# pc_rpimax30205_brk.net
KiCad netlist of a schematic drawn in EAGLE
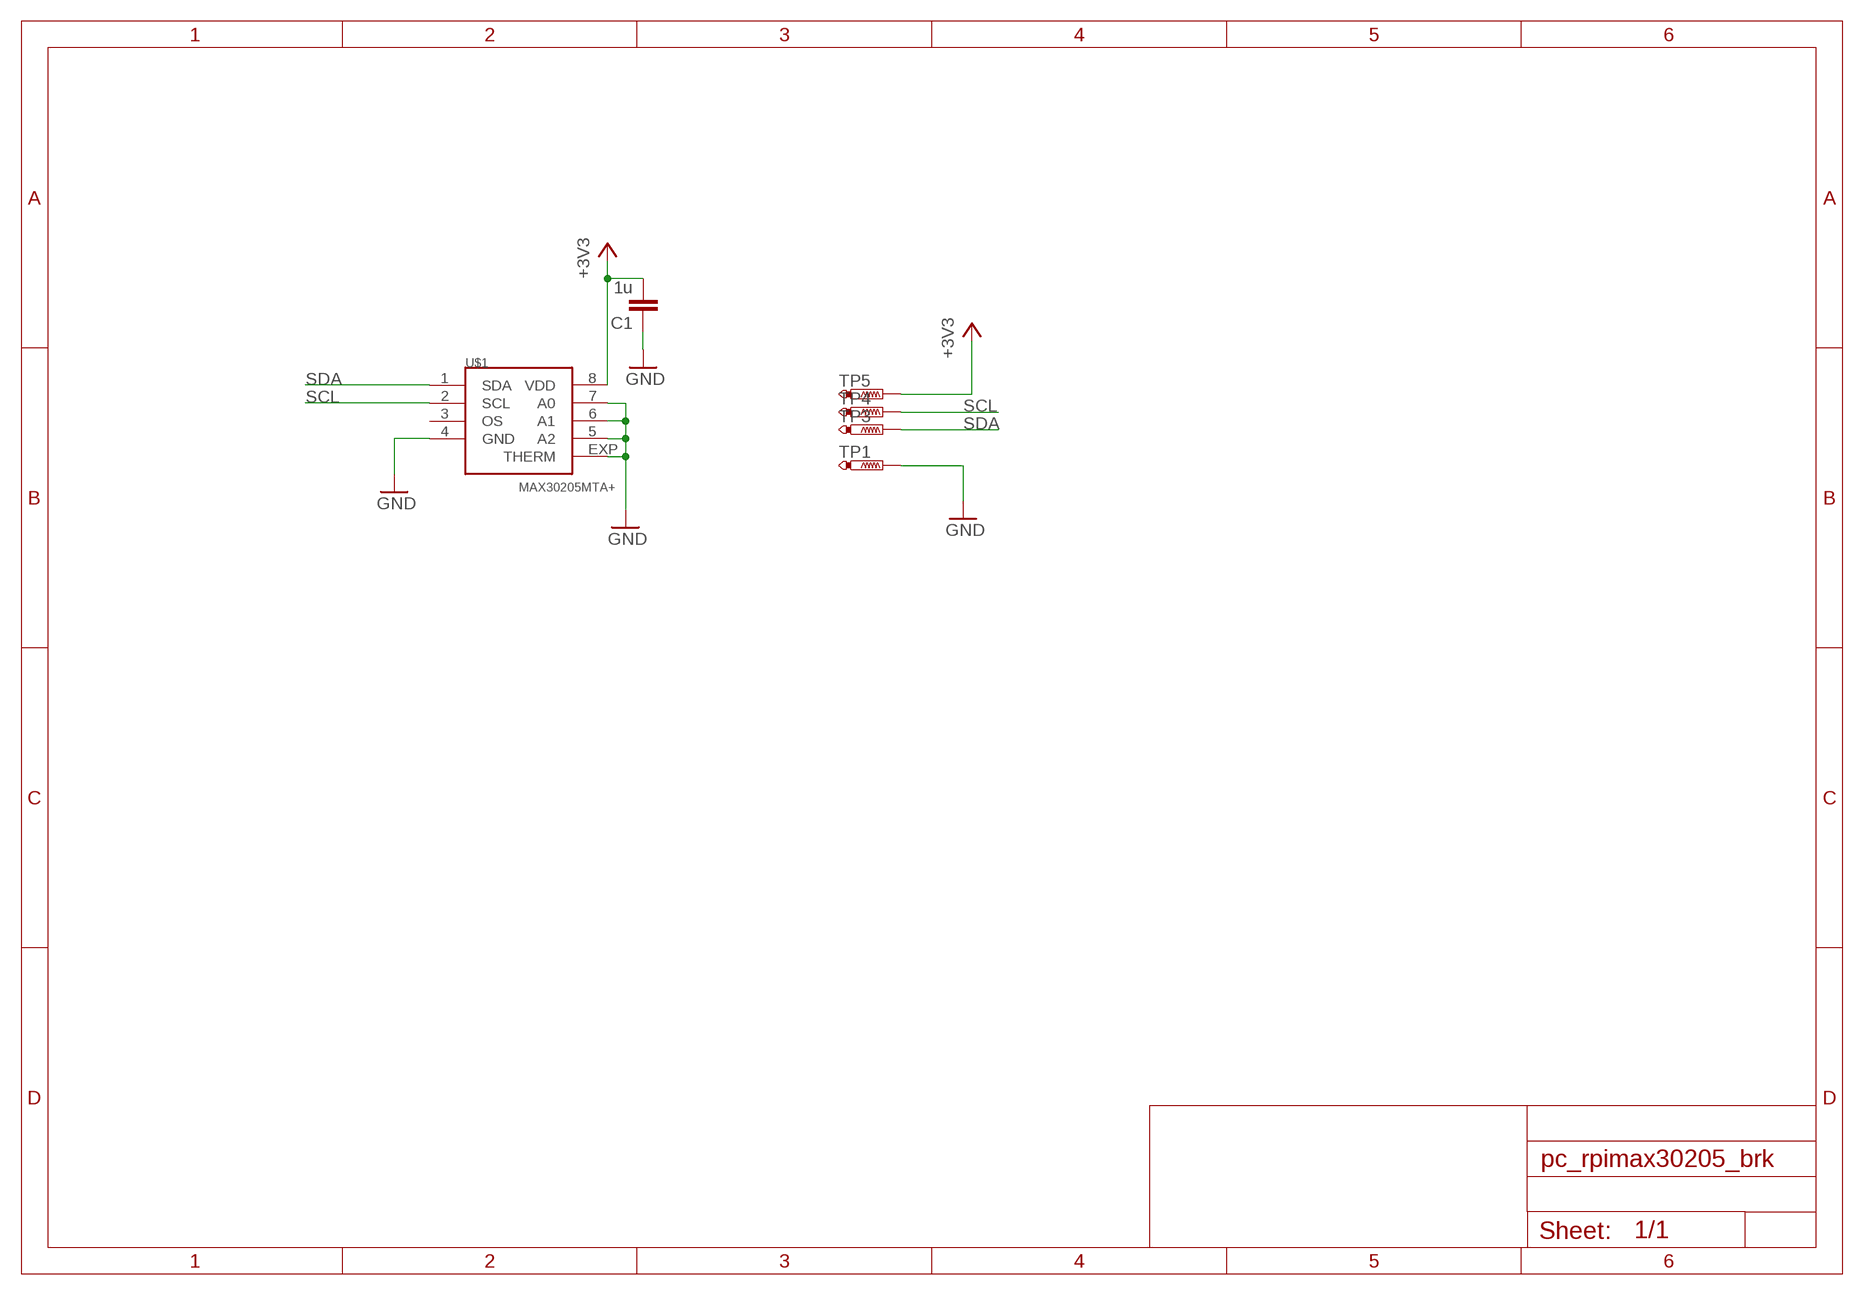
[diagram p0: schematic, sheet 1]

(export (version "E")
  (design (tool "Eeschema 10.0.6"))
  (components
    (comp (ref "C1")
      (value "1u")
      (footprint "eagle-import:C0805")
      (libsource (lib "eagle-import") (part "C-EUC0805"))
    )
    (comp (ref "TP1")
      (value "PTR1TP20SQ")
      (footprint "eagle-import:TP20SQ")
      (libsource (lib "eagle-import") (part "PTR1TP20SQ"))
    )
    (comp (ref "TP3")
      (value "PTR1TP20SQ")
      (footprint "eagle-import:TP20SQ")
      (libsource (lib "eagle-import") (part "PTR1TP20SQ"))
    )
    (comp (ref "TP4")
      (value "PTR1TP20SQ")
      (footprint "eagle-import:TP20SQ")
      (libsource (lib "eagle-import") (part "PTR1TP20SQ"))
    )
    (comp (ref "TP5")
      (value "PTR1TP20SQ")
      (footprint "eagle-import:TP20SQ")
      (libsource (lib "eagle-import") (part "PTR1TP20SQ"))
    )
    (comp (ref "U$1")
      (value "MAX30205MTA+")
      (footprint "eagle-import:TDFN-08")
      (libsource (lib "eagle-import") (part "MAX30205MTA+"))
    )
  )
  (nets
    (net (code "1") (name "+3V3") (class "Default")
      (node (ref "C1") (pin "2") (pinfunction "2_2") (pintype "passive"))
      (node (ref "TP5") (pin "TP") (pinfunction "TP_TP") (pintype "input"))
      (node (ref "U$1") (pin "8") (pinfunction "VDD_8") (pintype "bidirectional"))
    )
    (net (code "2") (name "/SCL") (class "Default")
      (node (ref "TP4") (pin "TP") (pinfunction "TP_TP") (pintype "input"))
      (node (ref "U$1") (pin "2") (pinfunction "SCL_2") (pintype "bidirectional"))
    )
    (net (code "3") (name "/SDA") (class "Default")
      (node (ref "TP3") (pin "TP") (pinfunction "TP_TP") (pintype "input"))
      (node (ref "U$1") (pin "1") (pinfunction "SDA_1") (pintype "bidirectional"))
    )
    (net (code "4") (name "GND") (class "Default")
      (node (ref "C1") (pin "1") (pinfunction "1_1") (pintype "passive"))
      (node (ref "TP1") (pin "TP") (pinfunction "TP_TP") (pintype "input"))
      (node (ref "U$1") (pin "4") (pinfunction "GND_4") (pintype "bidirectional"))
      (node (ref "U$1") (pin "5") (pinfunction "A2_5") (pintype "bidirectional"))
      (node (ref "U$1") (pin "6") (pinfunction "A1_6") (pintype "bidirectional"))
      (node (ref "U$1") (pin "7") (pinfunction "A0_7") (pintype "bidirectional"))
      (node (ref "U$1") (pin "EXP") (pinfunction "THERM_EXP") (pintype "bidirectional"))
    )
    (net (code "5") (name "unconnected-(U$1-OS-Pad3)") (class "Default")
      (node (ref "U$1") (pin "3") (pinfunction "OS_3") (pintype "bidirectional"))
    )
  )
)
